# Chamber_VIP_2.net
KiCad netlist of a schematic drawn in EAGLE
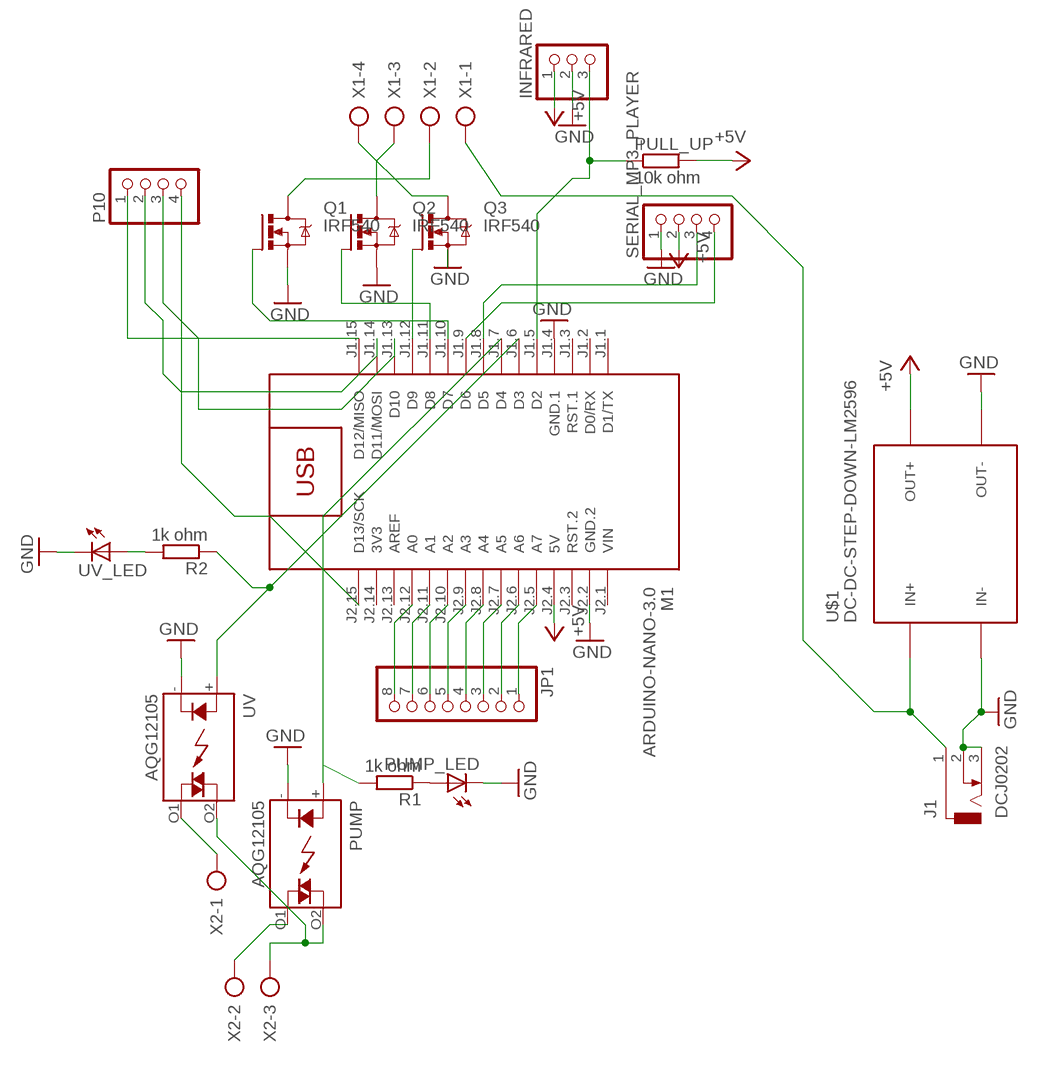
[diagram p0: schematic, sheet 1]

(export (version "E")
  (design (tool "Eeschema 10.0.6"))
  (components
    (comp (ref "INFRARED")
      (value "PINHD-1X3")
      (footprint "eagle-import:1X03")
      (libsource (lib "eagle-import") (part "PINHD-1X3"))
    )
    (comp (ref "J1")
      (value "DCJ0202")
      (footprint "eagle-import:DCJ0202")
      (libsource (lib "eagle-import") (part "DCJ0202"))
    )
    (comp (ref "JP1")
      (value "PINHD-1X8")
      (footprint "eagle-import:1X08")
      (libsource (lib "eagle-import") (part "PINHD-1X8"))
    )
    (comp (ref "M1")
      (value "ARDUINO-NANO-3.0")
      (footprint "eagle-import:ARDUINO-NANO-3.0")
      (libsource (lib "eagle-import") (part "ARDUINO-NANO-3.0"))
    )
    (comp (ref "P10")
      (value "PINHD-1X4")
      (footprint "eagle-import:1X04")
      (libsource (lib "eagle-import") (part "PINHD-1X4"))
    )
    (comp (ref "PULL_UP")
      (value "10k ohm")
      (footprint "eagle-import:0204_7")
      (libsource (lib "eagle-import") (part "R-EU_0204/7"))
    )
    (comp (ref "PUMP")
      (value "AQG12105")
      (footprint "eagle-import:AQG")
      (fields (field (name "MF") "AROMAT/ MATSUSHITA"))
      (libsource (lib "eagle-import") (part "AQG12105"))
    )
    (comp (ref "PUMP_LED")
      (value "LED5MM")
      (footprint "eagle-import:LED5MM")
      (libsource (lib "eagle-import") (part "LED5MM"))
    )
    (comp (ref "Q1")
      (value "IRF540")
      (footprint "eagle-import:TO220BV")
      (libsource (lib "eagle-import") (part "IRF540"))
    )
    (comp (ref "Q2")
      (value "IRF540")
      (footprint "eagle-import:TO220BV")
      (libsource (lib "eagle-import") (part "IRF540"))
    )
    (comp (ref "Q3")
      (value "IRF540")
      (footprint "eagle-import:TO220BV")
      (libsource (lib "eagle-import") (part "IRF540"))
    )
    (comp (ref "R1")
      (value "1k ohm")
      (footprint "eagle-import:0204_7")
      (libsource (lib "eagle-import") (part "R-EU_0204/7"))
    )
    (comp (ref "R2")
      (value "1k ohm")
      (footprint "eagle-import:0204_7")
      (libsource (lib "eagle-import") (part "R-EU_0204/7"))
    )
    (comp (ref "SERIAL_MP3_PLAYER")
      (value "PINHD-1X4")
      (footprint "eagle-import:1X04")
      (libsource (lib "eagle-import") (part "PINHD-1X4"))
    )
    (comp (ref "U$1")
      (value "DC-DC-STEP-DOWN-LM2596")
      (footprint "eagle-import:DC-DC-STEP-DOWN-LM2596")
      (libsource (lib "eagle-import") (part "DC-DC-STEP-DOWN-LM2596"))
    )
    (comp (ref "UV")
      (value "AQG12105")
      (footprint "eagle-import:AQG")
      (fields (field (name "MF") "AROMAT/ MATSUSHITA"))
      (libsource (lib "eagle-import") (part "AQG12105"))
    )
    (comp (ref "UV_LED")
      (value "LED5MM")
      (footprint "eagle-import:LED5MM")
      (libsource (lib "eagle-import") (part "LED5MM"))
    )
    (comp (ref "X1")
      (value "AK300/4")
      (footprint "eagle-import:AK300_4")
      (libsource (lib "eagle-import") (part "AK300/4"))
    )
    (comp (ref "X2")
      (value "AK300/3")
      (footprint "eagle-import:AK300_3")
      (libsource (lib "eagle-import") (part "AK300/3"))
    )
  )
  (nets
    (net (code "1") (name "+5V") (class "Default")
      (node (ref "INFRARED") (pin "1") (pinfunction "1_1") (pintype "passive"))
      (node (ref "M1") (pin "J2.4") (pinfunction "5V_J2.4") (pintype "power_in"))
      (node (ref "PULL_UP") (pin "2") (pinfunction "2_2") (pintype "passive"))
      (node (ref "SERIAL_MP3_PLAYER") (pin "2") (pinfunction "2_2") (pintype "passive"))
      (node (ref "U$1") (pin "OUT+") (pinfunction "OUT+_OUT+") (pintype "bidirectional"))
    )
    (net (code "2") (name "/3V3") (class "Default")
      (node (ref "M1") (pin "J2.14") (pinfunction "3V3_J2.14") (pintype "power_in"))
    )
    (net (code "3") (name "/VIN") (class "Default")
      (node (ref "M1") (pin "J2.1") (pinfunction "VIN_J2.1") (pintype "power_in"))
    )
    (net (code "4") (name "GND") (class "Default")
      (node (ref "INFRARED") (pin "2") (pinfunction "2_2") (pintype "passive"))
      (node (ref "J1") (pin "2") (pinfunction "2_2") (pintype "passive"))
      (node (ref "J1") (pin "3") (pinfunction "3_3") (pintype "passive"))
      (node (ref "M1") (pin "J1.4") (pinfunction "GND.1_J1.4") (pintype "power_in"))
      (node (ref "M1") (pin "J2.2") (pinfunction "GND.2_J2.2") (pintype "power_in"))
      (node (ref "PUMP") (pin "-") (pinfunction "K_-") (pintype "passive"))
      (node (ref "PUMP_LED") (pin "K") (pinfunction "C_K") (pintype "passive"))
      (node (ref "Q1") (pin "S") (pinfunction "S_S") (pintype "passive"))
      (node (ref "Q2") (pin "S") (pinfunction "S_S") (pintype "passive"))
      (node (ref "Q3") (pin "S") (pinfunction "S_S") (pintype "passive"))
      (node (ref "SERIAL_MP3_PLAYER") (pin "1") (pinfunction "1_1") (pintype "passive"))
      (node (ref "U$1") (pin "IN-") (pinfunction "IN-_IN-") (pintype "bidirectional"))
      (node (ref "U$1") (pin "OUT-") (pinfunction "OUT-_OUT-") (pintype "bidirectional"))
      (node (ref "UV") (pin "-") (pinfunction "K_-") (pintype "passive"))
      (node (ref "UV_LED") (pin "K") (pinfunction "C_K") (pintype "passive"))
    )
    (net (code "5") (name "Net-(M1-A0)") (class "Default")
      (node (ref "JP1") (pin "8") (pinfunction "8_8") (pintype "passive"))
      (node (ref "M1") (pin "J2.12") (pinfunction "A0_J2.12") (pintype "bidirectional"))
    )
    (net (code "6") (name "Net-(M1-A1)") (class "Default")
      (node (ref "JP1") (pin "7") (pinfunction "7_7") (pintype "passive"))
      (node (ref "M1") (pin "J2.11") (pinfunction "A1_J2.11") (pintype "bidirectional"))
    )
    (net (code "7") (name "Net-(M1-A2)") (class "Default")
      (node (ref "JP1") (pin "6") (pinfunction "6_6") (pintype "passive"))
      (node (ref "M1") (pin "J2.10") (pinfunction "A2_J2.10") (pintype "bidirectional"))
    )
    (net (code "8") (name "Net-(M1-A3)") (class "Default")
      (node (ref "JP1") (pin "5") (pinfunction "5_5") (pintype "passive"))
      (node (ref "M1") (pin "J2.9") (pinfunction "A3_J2.9") (pintype "bidirectional"))
    )
    (net (code "9") (name "Net-(M1-A4)") (class "Default")
      (node (ref "JP1") (pin "4") (pinfunction "4_4") (pintype "passive"))
      (node (ref "M1") (pin "J2.8") (pinfunction "A4_J2.8") (pintype "bidirectional"))
    )
    (net (code "10") (name "Net-(M1-A5)") (class "Default")
      (node (ref "JP1") (pin "3") (pinfunction "3_3") (pintype "passive"))
      (node (ref "M1") (pin "J2.7") (pinfunction "A5_J2.7") (pintype "bidirectional"))
    )
    (net (code "11") (name "Net-(M1-A6)") (class "Default")
      (node (ref "JP1") (pin "2") (pinfunction "2_2") (pintype "passive"))
      (node (ref "M1") (pin "J2.6") (pinfunction "A6_J2.6") (pintype "bidirectional"))
    )
    (net (code "12") (name "Net-(M1-A7)") (class "Default")
      (node (ref "JP1") (pin "1") (pinfunction "1_1") (pintype "passive"))
      (node (ref "M1") (pin "J2.5") (pinfunction "A7_J2.5") (pintype "bidirectional"))
    )
    (net (code "13") (name "Net-(M1-D2)") (class "Default")
      (node (ref "INFRARED") (pin "3") (pinfunction "3_3") (pintype "passive"))
      (node (ref "M1") (pin "J1.5") (pinfunction "D2_J1.5") (pintype "bidirectional"))
      (node (ref "PULL_UP") (pin "1") (pinfunction "1_1") (pintype "passive"))
    )
    (net (code "14") (name "Net-(M1-D3)") (class "Default")
      (node (ref "M1") (pin "J1.6") (pinfunction "D3_J1.6") (pintype "bidirectional"))
      (node (ref "R2") (pin "1") (pinfunction "1_1") (pintype "passive"))
      (node (ref "UV") (pin "+") (pinfunction "A_+") (pintype "passive"))
    )
    (net (code "15") (name "Net-(M1-D4)") (class "Default")
      (node (ref "M1") (pin "J1.7") (pinfunction "D4_J1.7") (pintype "bidirectional"))
      (node (ref "PUMP") (pin "+") (pinfunction "A_+") (pintype "passive"))
      (node (ref "R1") (pin "2") (pinfunction "2_2") (pintype "passive"))
    )
    (net (code "16") (name "Net-(M1-D5)") (class "Default")
      (node (ref "M1") (pin "J1.8") (pinfunction "D5_J1.8") (pintype "bidirectional"))
      (node (ref "SERIAL_MP3_PLAYER") (pin "3") (pinfunction "3_3") (pintype "passive"))
    )
    (net (code "17") (name "Net-(M1-D6)") (class "Default")
      (node (ref "M1") (pin "J1.9") (pinfunction "D6_J1.9") (pintype "bidirectional"))
      (node (ref "SERIAL_MP3_PLAYER") (pin "4") (pinfunction "4_4") (pintype "passive"))
    )
    (net (code "18") (name "Net-(M1-D7)") (class "Default")
      (node (ref "M1") (pin "J1.10") (pinfunction "D7_J1.10") (pintype "bidirectional"))
      (node (ref "Q1") (pin "G") (pinfunction "G_G") (pintype "passive"))
    )
    (net (code "19") (name "Net-(M1-D8)") (class "Default")
      (node (ref "M1") (pin "J1.11") (pinfunction "D8_J1.11") (pintype "bidirectional"))
      (node (ref "Q2") (pin "G") (pinfunction "G_G") (pintype "passive"))
    )
    (net (code "20") (name "Net-(M1-D9)") (class "Default")
      (node (ref "M1") (pin "J1.12") (pinfunction "D9_J1.12") (pintype "bidirectional"))
      (node (ref "Q3") (pin "G") (pinfunction "G_G") (pintype "passive"))
    )
    (net (code "21") (name "Net-(M1-D10)") (class "Default")
      (node (ref "M1") (pin "J1.13") (pinfunction "D10_J1.13") (pintype "bidirectional"))
      (node (ref "P10") (pin "3") (pinfunction "3_3") (pintype "passive"))
    )
    (net (code "22") (name "Net-(M1-D11{slash}MOSI)") (class "Default")
      (node (ref "M1") (pin "J1.14") (pinfunction "D11/MOSI_J1.14") (pintype "bidirectional"))
      (node (ref "P10") (pin "2") (pinfunction "2_2") (pintype "passive"))
    )
    (net (code "23") (name "Net-(M1-D12{slash}MISO)") (class "Default")
      (node (ref "M1") (pin "J1.15") (pinfunction "D12/MISO_J1.15") (pintype "bidirectional"))
      (node (ref "P10") (pin "1") (pinfunction "1_1") (pintype "passive"))
    )
    (net (code "24") (name "Net-(M1-D13{slash}SCK)") (class "Default")
      (node (ref "M1") (pin "J2.15") (pinfunction "D13/SCK_J2.15") (pintype "bidirectional"))
      (node (ref "P10") (pin "4") (pinfunction "4_4") (pintype "passive"))
    )
    (net (code "25") (name "Net-(PUMP-DS1)") (class "Default")
      (node (ref "PUMP") (pin "O2") (pinfunction "DS1_O2") (pintype "passive"))
      (node (ref "UV") (pin "O2") (pinfunction "DS1_O2") (pintype "passive"))
      (node (ref "X2") (pin "3") (pinfunction "KL_3") (pintype "passive"))
    )
    (net (code "26") (name "Net-(PUMP-DS2)") (class "Default")
      (node (ref "PUMP") (pin "O1") (pinfunction "DS2_O1") (pintype "passive"))
      (node (ref "X2") (pin "2") (pinfunction "KL_2") (pintype "passive"))
    )
    (net (code "27") (name "Net-(PUMP_LED-PadA)") (class "Default")
      (node (ref "PUMP_LED") (pin "A") (pinfunction "A_A") (pintype "passive"))
      (node (ref "R1") (pin "1") (pinfunction "1_1") (pintype "passive"))
    )
    (net (code "28") (name "Net-(R2-Pad2)") (class "Default")
      (node (ref "R2") (pin "2") (pinfunction "2_2") (pintype "passive"))
      (node (ref "UV_LED") (pin "A") (pinfunction "A_A") (pintype "passive"))
    )
    (net (code "29") (name "Net-(UV-DS2)") (class "Default")
      (node (ref "UV") (pin "O1") (pinfunction "DS2_O1") (pintype "passive"))
      (node (ref "X2") (pin "1") (pinfunction "KL_1") (pintype "passive"))
    )
    (net (code "30") (name "Net-(X1A-KL)") (class "Default")
      (node (ref "J1") (pin "1") (pinfunction "1_1") (pintype "passive"))
      (node (ref "U$1") (pin "IN+") (pinfunction "IN+_IN+") (pintype "bidirectional"))
      (node (ref "X1") (pin "1") (pinfunction "KL_1") (pintype "passive"))
    )
    (net (code "31") (name "Net-(X1B-KL)") (class "Default")
      (node (ref "Q1") (pin "D") (pinfunction "D_D") (pintype "passive"))
      (node (ref "X1") (pin "2") (pinfunction "KL_2") (pintype "passive"))
    )
    (net (code "32") (name "Net-(X1C-KL)") (class "Default")
      (node (ref "Q2") (pin "D") (pinfunction "D_D") (pintype "passive"))
      (node (ref "X1") (pin "3") (pinfunction "KL_3") (pintype "passive"))
    )
    (net (code "33") (name "Net-(X1D-KL)") (class "Default")
      (node (ref "Q3") (pin "D") (pinfunction "D_D") (pintype "passive"))
      (node (ref "X1") (pin "4") (pinfunction "KL_4") (pintype "passive"))
    )
    (net (code "34") (name "unconnected-(M1-AREF-PadJ2.13)") (class "Default")
      (node (ref "M1") (pin "J2.13") (pinfunction "AREF_J2.13") (pintype "bidirectional"))
    )
    (net (code "35") (name "unconnected-(M1-D0{slash}RX-PadJ1.2)") (class "Default")
      (node (ref "M1") (pin "J1.2") (pinfunction "D0/RX_J1.2") (pintype "bidirectional"))
    )
    (net (code "36") (name "unconnected-(M1-D1{slash}TX-PadJ1.1)") (class "Default")
      (node (ref "M1") (pin "J1.1") (pinfunction "D1/TX_J1.1") (pintype "bidirectional"))
    )
    (net (code "37") (name "unconnected-(M1-RST.1-PadJ1.3)") (class "Default")
      (node (ref "M1") (pin "J1.3") (pinfunction "RST.1_J1.3") (pintype "bidirectional"))
    )
    (net (code "38") (name "unconnected-(M1-RST.2-PadJ2.3)") (class "Default")
      (node (ref "M1") (pin "J2.3") (pinfunction "RST.2_J2.3") (pintype "bidirectional"))
    )
  )
)
